# amebot.net
KiCad netlist of a schematic drawn in EAGLE
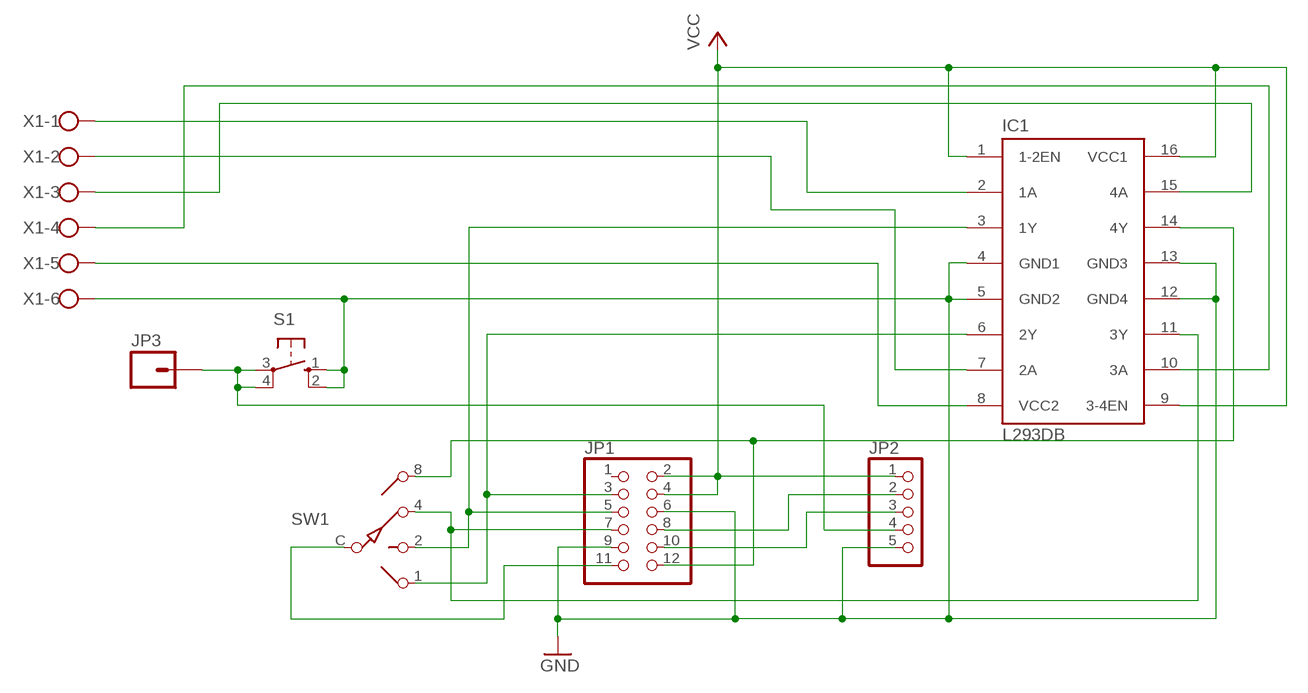
[diagram p0: schematic, sheet 1]

(export (version "E")
  (design (tool "Eeschema 10.0.6"))
  (components
    (comp (ref "IC1")
      (value "L293DB")
      (footprint "eagle-import:DIL16VAR")
      (libsource (lib "eagle-import") (part "L293DB"))
    )
    (comp (ref "JP1")
      (value "PINHD-2X6")
      (footprint "eagle-import:2X06")
      (libsource (lib "eagle-import") (part "PINHD-2X6"))
    )
    (comp (ref "JP2")
      (value "PINHD-1X5")
      (footprint "eagle-import:1X05")
      (libsource (lib "eagle-import") (part "PINHD-1X5"))
    )
    (comp (ref "JP3")
      (value "M01PTH_LONGPAD")
      (footprint "eagle-import:1X01_LONGPAD")
      (libsource (lib "eagle-import") (part "M01PTH_LONGPAD"))
    )
    (comp (ref "S1")
      (value "10-XX")
      (footprint "eagle-import:B3F-10XX")
      (fields (field (name "MPN") "B3F-1000"))
      (libsource (lib "eagle-import") (part "10-XX"))
    )
    (comp (ref "SW1")
      (value "SW-C10")
      (footprint "eagle-import:SW-C10")
      (libsource (lib "eagle-import") (part "SW-C10"))
    )
    (comp (ref "X1")
      (value "W237-6")
      (footprint "eagle-import:W237-6")
      (libsource (lib "eagle-import") (part "W237-6"))
    )
  )
  (nets
    (net (code "1") (name "GND") (class "Default")
      (node (ref "IC1") (pin "12") (pinfunction "GND4_12") (pintype "power_in"))
      (node (ref "IC1") (pin "13") (pinfunction "GND3_13") (pintype "power_in"))
      (node (ref "IC1") (pin "4") (pinfunction "GND1_4") (pintype "power_in"))
      (node (ref "IC1") (pin "5") (pinfunction "GND2_5") (pintype "power_in"))
      (node (ref "JP1") (pin "6") (pinfunction "6_6") (pintype "passive"))
      (node (ref "JP1") (pin "9") (pinfunction "9_9") (pintype "passive"))
      (node (ref "JP2") (pin "5") (pinfunction "5_5") (pintype "passive"))
      (node (ref "S1") (pin "1") (pinfunction "S_1") (pintype "passive"))
      (node (ref "S1") (pin "2") (pinfunction "S1_2") (pintype "passive"))
      (node (ref "X1") (pin "6") (pinfunction "KL_6") (pintype "passive"))
    )
    (net (code "2") (name "Net-(IC1-1A)") (class "Default")
      (node (ref "IC1") (pin "2") (pinfunction "1A_2") (pintype "input"))
      (node (ref "X1") (pin "1") (pinfunction "KL_1") (pintype "passive"))
    )
    (net (code "3") (name "Net-(IC1-1Y)") (class "Default")
      (node (ref "IC1") (pin "3") (pinfunction "1Y_3") (pintype "output"))
      (node (ref "JP1") (pin "5") (pinfunction "5_5") (pintype "passive"))
      (node (ref "SW1") (pin "2") (pinfunction "2_2") (pintype "passive"))
    )
    (net (code "4") (name "Net-(IC1-2A)") (class "Default")
      (node (ref "IC1") (pin "7") (pinfunction "2A_7") (pintype "input"))
      (node (ref "X1") (pin "2") (pinfunction "KL_2") (pintype "passive"))
    )
    (net (code "5") (name "Net-(IC1-2Y)") (class "Default")
      (node (ref "IC1") (pin "6") (pinfunction "2Y_6") (pintype "output"))
      (node (ref "JP1") (pin "3") (pinfunction "3_3") (pintype "passive"))
      (node (ref "SW1") (pin "1") (pinfunction "1_1") (pintype "passive"))
    )
    (net (code "6") (name "Net-(IC1-3A)") (class "Default")
      (node (ref "IC1") (pin "10") (pinfunction "3A_10") (pintype "input"))
      (node (ref "X1") (pin "4") (pinfunction "KL_4") (pintype "passive"))
    )
    (net (code "7") (name "Net-(IC1-3Y)") (class "Default")
      (node (ref "IC1") (pin "11") (pinfunction "3Y_11") (pintype "output"))
      (node (ref "JP1") (pin "7") (pinfunction "7_7") (pintype "passive"))
      (node (ref "SW1") (pin "4") (pinfunction "4_4") (pintype "passive"))
    )
    (net (code "8") (name "Net-(IC1-4A)") (class "Default")
      (node (ref "IC1") (pin "15") (pinfunction "4A_15") (pintype "input"))
      (node (ref "X1") (pin "3") (pinfunction "KL_3") (pintype "passive"))
    )
    (net (code "9") (name "Net-(IC1-4Y)") (class "Default")
      (node (ref "IC1") (pin "14") (pinfunction "4Y_14") (pintype "output"))
      (node (ref "JP1") (pin "12") (pinfunction "12_12") (pintype "passive"))
      (node (ref "SW1") (pin "8") (pinfunction "8_8") (pintype "passive"))
    )
    (net (code "10") (name "Net-(IC1-VCC2)") (class "Default")
      (node (ref "IC1") (pin "8") (pinfunction "VCC2_8") (pintype "power_in"))
      (node (ref "X1") (pin "5") (pinfunction "KL_5") (pintype "passive"))
    )
    (net (code "11") (name "Net-(JP1-Pad8)") (class "Default")
      (node (ref "JP1") (pin "8") (pinfunction "8_8") (pintype "passive"))
      (node (ref "JP2") (pin "2") (pinfunction "2_2") (pintype "passive"))
    )
    (net (code "12") (name "Net-(JP1-Pad10)") (class "Default")
      (node (ref "JP1") (pin "10") (pinfunction "10_10") (pintype "passive"))
      (node (ref "JP2") (pin "3") (pinfunction "3_3") (pintype "passive"))
    )
    (net (code "13") (name "Net-(JP1-Pad11)") (class "Default")
      (node (ref "JP1") (pin "11") (pinfunction "11_11") (pintype "passive"))
      (node (ref "SW1") (pin "C") (pinfunction "C_C") (pintype "passive"))
    )
    (net (code "14") (name "Net-(S1-P)") (class "Default")
      (node (ref "JP2") (pin "4") (pinfunction "4_4") (pintype "passive"))
      (node (ref "JP3") (pin "1") (pinfunction "1_1") (pintype "passive"))
      (node (ref "S1") (pin "3") (pinfunction "P_3") (pintype "passive"))
      (node (ref "S1") (pin "4") (pinfunction "P1_4") (pintype "passive"))
    )
    (net (code "15") (name "VCC") (class "Default")
      (node (ref "IC1") (pin "1") (pinfunction "1-2EN_1") (pintype "input"))
      (node (ref "IC1") (pin "16") (pinfunction "VCC1_16") (pintype "power_in"))
      (node (ref "IC1") (pin "9") (pinfunction "3-4EN_9") (pintype "input"))
      (node (ref "JP1") (pin "2") (pinfunction "2_2") (pintype "passive"))
      (node (ref "JP1") (pin "4") (pinfunction "4_4") (pintype "passive"))
      (node (ref "JP2") (pin "1") (pinfunction "1_1") (pintype "passive"))
    )
    (net (code "16") (name "unconnected-(JP1-Pad1)") (class "Default")
      (node (ref "JP1") (pin "1") (pinfunction "1_1") (pintype "passive"))
    )
  )
)
